# 04_POWER.net
KiCad netlist of a schematic drawn in Altium Designer
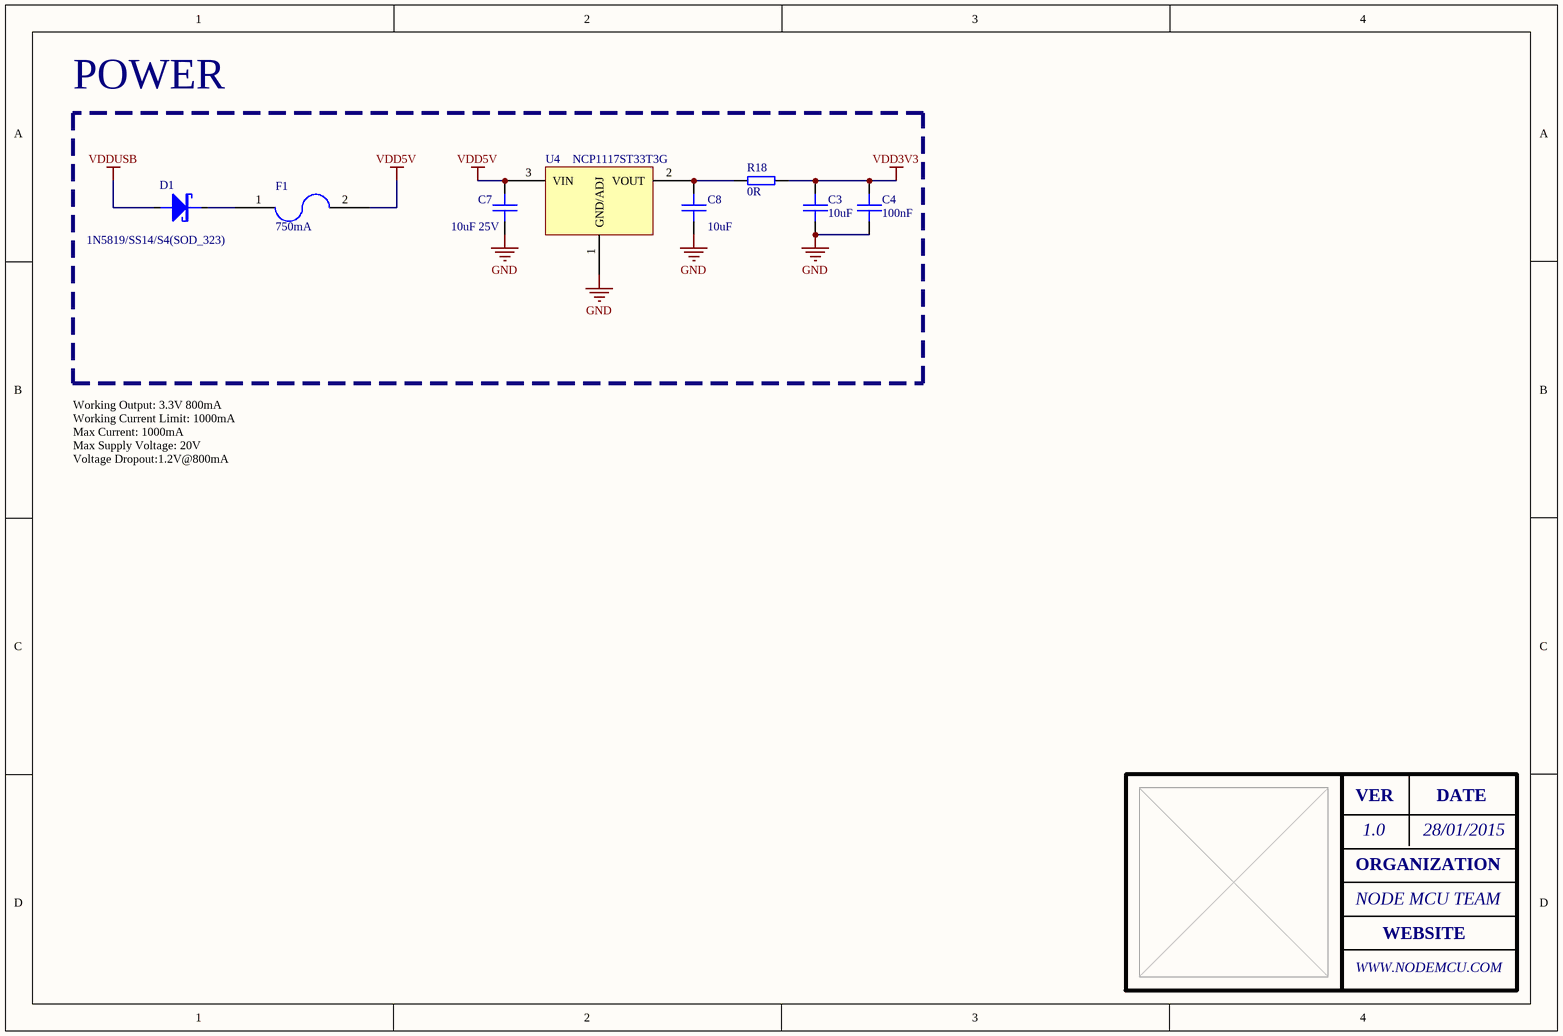
[diagram p0: 04_POWER.SchDoc]

(export (version "E")
  (design (tool "Eeschema 10.0.6"))
  (components
    (comp (ref "C3")
      (value "10uF")
      (footprint "SMT_C_0402")
      (description "Surface mount capacitor 0402")
      (libsource (lib "Vowstar_Basic_Device") (part "SMT_C_0402"))
    )
    (comp (ref "C4")
      (value "100nF")
      (footprint "SMT_C_0402")
      (description "Surface mount capacitor 0402")
      (libsource (lib "Vowstar_Basic_Device") (part "SMT_C_0402"))
    )
    (comp (ref "C7")
      (value "10uF 25V")
      (footprint "SMT_C_0805")
      (description "Surface mount capacitor 0805")
      (libsource (lib "Vowstar_Basic_Device") (part "SMT_C_0805"))
    )
    (comp (ref "C8")
      (value "10uF")
      (footprint "SMT_C_0402")
      (description "Surface mount capacitor 0402")
      (libsource (lib "Vowstar_Basic_Device") (part "SMT_C_0402"))
    )
    (comp (ref "D1")
      (value "1N5819/SS14/S4(SOD_323)")
      (footprint "SMT_DIODE_SOD_323")
      (description "Surface mount schottky diode SOD-323(0805) Package")
      (libsource (lib "Vowstar_Basic_Device") (part "SMT_DIODE_SCHOTTKY_SOD_323"))
    )
    (comp (ref "F1")
      (value "750mA")
      (footprint "FUSE0603")
      (description "LITTELFUSE - 0603L035YR - RESETTABLE FUSE, PTC, 40A, 6V, 0605")
      (fields
        (field (name "MANUFACTURER") "LITTELFUSE")
        (field (name "MANUFACTURER PART NUMBER") "0603L035YR")
      )
      (libsource (lib "Fuse") (part "PTC FUSE 750mA"))
    )
    (comp (ref "R18")
      (value "0R")
      (footprint "SMT_R_0402")
      (description "Surface mount resistor 0402")
      (libsource (lib "Vowstar_Basic_Device") (part "SMT_R_0402"))
    )
    (comp (ref "U4")
      (value "NCP1117ST33T3G")
      (footprint "SOT-223")
      (description "NCP1117, NCV1117. 1.0 A Low-Dropout Positive  Fixed and Adjustable  Voltage Regulators")
      (libsource (lib "Vowstar_IC_General") (part "NCP1117"))
    )
  )
  (nets
    (net (code "1") (name "GND") (class "Default")
      (node (ref "C3") (pin "2") (pinfunction "2_2") (pintype "passive"))
      (node (ref "C4") (pin "2") (pinfunction "2_2") (pintype "passive"))
      (node (ref "C7") (pin "2") (pinfunction "2_2") (pintype "passive"))
      (node (ref "C8") (pin "2") (pinfunction "2_2") (pintype "passive"))
      (node (ref "U4") (pin "1") (pinfunction "GND/ADJ_1") (pintype "passive"))
    )
    (net (code "2") (name "Net-(D1-K)") (class "Default")
      (node (ref "D1") (pin "2") (pinfunction "K_2") (pintype "passive"))
      (node (ref "F1") (pin "1") (pinfunction "1_1") (pintype "open_collector"))
    )
    (net (code "3") (name "Net-(U4-VOUT)") (class "Default")
      (node (ref "C8") (pin "1") (pinfunction "1_1") (pintype "passive"))
      (node (ref "R18") (pin "2") (pinfunction "2_2") (pintype "passive"))
      (node (ref "U4") (pin "2") (pinfunction "VOUT_2") (pintype "passive"))
    )
    (net (code "4") (name "VDD3V3") (class "Default")
      (node (ref "C3") (pin "1") (pinfunction "1_1") (pintype "passive"))
      (node (ref "C4") (pin "1") (pinfunction "1_1") (pintype "passive"))
      (node (ref "R18") (pin "1") (pinfunction "1_1") (pintype "passive"))
    )
    (net (code "5") (name "VDD5V") (class "Default")
      (node (ref "C7") (pin "1") (pinfunction "1_1") (pintype "passive"))
      (node (ref "F1") (pin "2") (pinfunction "2_2") (pintype "open_collector"))
      (node (ref "U4") (pin "3") (pinfunction "VIN_3") (pintype "passive"))
    )
    (net (code "6") (name "VDDUSB") (class "Default")
      (node (ref "D1") (pin "1") (pinfunction "A_1") (pintype "passive"))
    )
  )
)
